# 3V3-CAN.net
KiCad netlist of a schematic drawn in Altium Designer
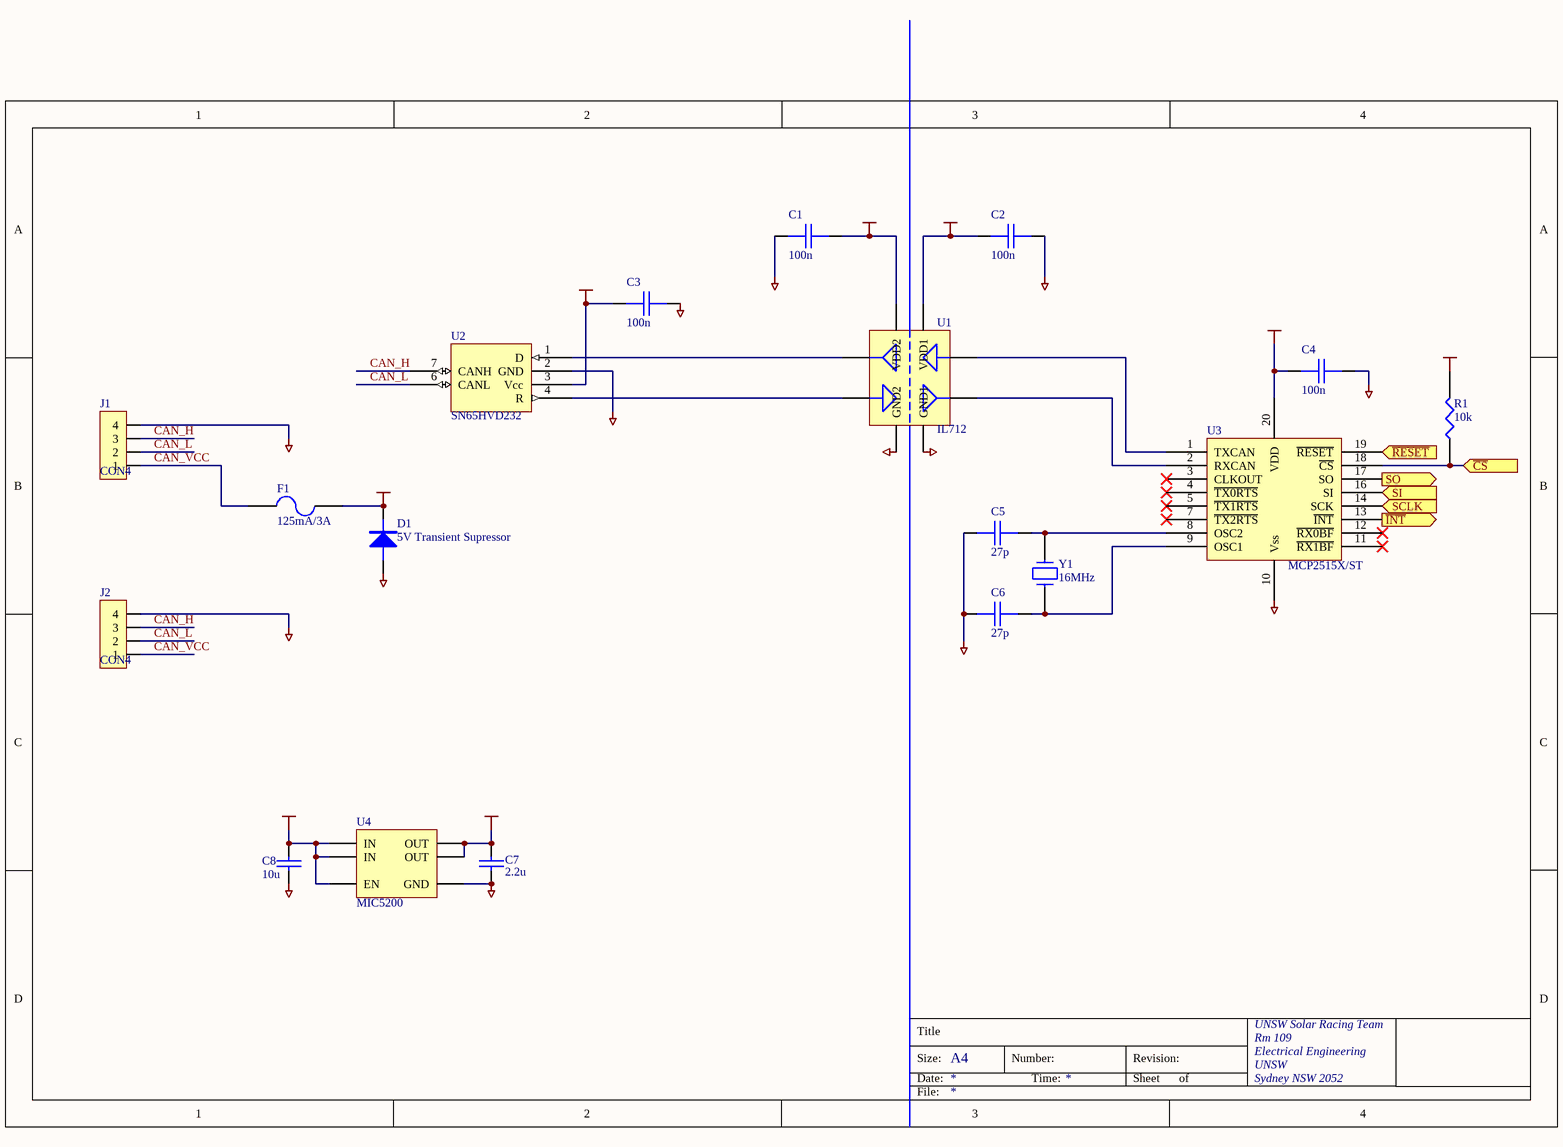
[diagram p0: 3V3-CAN.SchDoc]

(export (version "E")
  (design (tool "Eeschema 10.0.6"))
  (components
    (comp (ref "C1")
      (value "100n")
      (footprint "0603")
      (description "Capacitor")
      (libsource (lib "*") (part "CAP"))
    )
    (comp (ref "C2")
      (value "100n")
      (footprint "0603")
      (description "Capacitor")
      (libsource (lib "*") (part "CAP"))
    )
    (comp (ref "C3")
      (value "100n")
      (footprint "0603")
      (description "Capacitor")
      (libsource (lib "*") (part "CAP"))
    )
    (comp (ref "C4")
      (value "100n")
      (footprint "0603")
      (description "Capacitor")
      (libsource (lib "*") (part "CAP"))
    )
    (comp (ref "C5")
      (value "27p")
      (footprint "0603")
      (description "Capacitor")
      (libsource (lib "*") (part "CAP"))
    )
    (comp (ref "C6")
      (value "27p")
      (footprint "0603")
      (description "Capacitor")
      (libsource (lib "*") (part "CAP"))
    )
    (comp (ref "C7")
      (value "2.2u")
      (footprint "MCCT-CASEA")
      (description "Capacitor")
      (libsource (lib "") (part "CAP_1"))
    )
    (comp (ref "C8")
      (value "10u")
      (footprint "MCCT-CASEB")
      (description "Capacitor")
      (libsource (lib "") (part "CAP_1"))
    )
    (comp (ref "D1")
      (value "5V Transient Supressor")
      (footprint "SMA")
      (description "Diode")
      (libsource (lib "RCLDQ") (part "DIODE"))
    )
    (comp (ref "F1")
      (value "125mA/3A")
      (footprint "LITTELFUSE-154")
      (description "Fuse")
      (libsource (lib "*") (part "FUSE2"))
    )
    (comp (ref "J1")
      (value "CON4")
      (footprint "WEIDMULLER-SL3.5/4/90G")
      (description "Connector")
      (libsource (lib "Connectors") (part "CON4"))
    )
    (comp (ref "J2")
      (value "CON4")
      (footprint "WEIDMULLER-SL3.5/4/90G")
      (description "Connector")
      (libsource (lib "Connectors") (part "CON4"))
    )
    (comp (ref "R1") (value "10k") (footprint "0603") (libsource (lib "*") (part "RES1")))
    (comp (ref "U1")
      (value "IL712")
      (footprint "SO8")
      (description "IL712 Optoisolator - www.nve.com")
      (fields (field (name "PART FIELD 4") "simon.cope@tradetech.co.nz"))
      (libsource (lib "*") (part "IL712"))
    )
    (comp (ref "U2")
      (value "SN65HVD232")
      (footprint "SO8")
      (description "3.3V CAN Transciever")
      (libsource (lib "*") (part "SN65HVD232"))
    )
    (comp (ref "U3")
      (value "MCP2515X/ST")
      (footprint "TSSOP20")
      (description "MCP2510 CAN Controller")
      (libsource (lib "CAN") (part "MCP2515X/ST"))
    )
    (comp (ref "U4")
      (value "MIC5200")
      (footprint "SO8")
      (description "MIC5200 - SO8")
      (libsource (lib "*") (part "MIC5200"))
    )
    (comp (ref "Y1")
      (value "16MHz")
      (footprint "HC49/4H")
      (description "Crystal")
      (libsource (lib "*") (part "CRYSTAL"))
    )
  )
  (nets
    (net (code "1") (name "/CAN_H") (class "Default")
      (node (ref "J1") (pin "3") (pinfunction "3_3") (pintype "passive"))
      (node (ref "J2") (pin "3") (pinfunction "3_3") (pintype "passive"))
      (node (ref "U2") (pin "7") (pinfunction "CANH_7") (pintype "bidirectional"))
    )
    (net (code "2") (name "/CAN_L") (class "Default")
      (node (ref "J1") (pin "2") (pinfunction "2_2") (pintype "passive"))
      (node (ref "J2") (pin "2") (pinfunction "2_2") (pintype "passive"))
      (node (ref "U2") (pin "6") (pinfunction "CANL_6") (pintype "bidirectional"))
    )
    (net (code "3") (name "/CAN_VCC") (class "Default")
      (node (ref "F1") (pin "1") (pinfunction "1_1") (pintype "passive"))
      (node (ref "J1") (pin "1") (pinfunction "1_1") (pintype "passive"))
      (node (ref "J2") (pin "1") (pinfunction "1_1") (pintype "passive"))
    )
    (net (code "4") (name "/SCLK") (class "Default")
      (node (ref "U3") (pin "14") (pinfunction "SCK_14") (pintype "passive"))
    )
    (net (code "5") (name "/SI") (class "Default")
      (node (ref "U3") (pin "16") (pinfunction "SI_16") (pintype "passive"))
    )
    (net (code "6") (name "/SO") (class "Default")
      (node (ref "U3") (pin "17") (pinfunction "SO_17") (pintype "passive"))
    )
    (net (code "7") (name "/~{CS}") (class "Default")
      (node (ref "R1") (pin "1") (pinfunction "1_1") (pintype "passive"))
      (node (ref "U3") (pin "18") (pinfunction "~{CS}_18") (pintype "passive"))
    )
    (net (code "8") (name "/~{INT}") (class "Default")
      (node (ref "U3") (pin "13") (pinfunction "~{INT}_13") (pintype "passive"))
    )
    (net (code "9") (name "/~{RESET}") (class "Default")
      (node (ref "U3") (pin "19") (pinfunction "~{RESET}_19") (pintype "passive"))
    )
    (net (code "10") (name "3V3") (class "Default")
      (node (ref "C2") (pin "2") (pinfunction "2_2") (pintype "passive"))
      (node (ref "C4") (pin "1") (pinfunction "1_1") (pintype "passive"))
      (node (ref "R1") (pin "2") (pinfunction "2_2") (pintype "passive"))
      (node (ref "U1") (pin "1") (pinfunction "VDD1_1") (pintype "passive"))
      (node (ref "U3") (pin "20") (pinfunction "VDD_20") (pintype "passive"))
    )
    (net (code "11") (name "CAN_3V3") (class "Default")
      (node (ref "C1") (pin "2") (pinfunction "2_2") (pintype "passive"))
      (node (ref "C3") (pin "2") (pinfunction "2_2") (pintype "passive"))
      (node (ref "C7") (pin "2") (pinfunction "2_2") (pintype "passive"))
      (node (ref "U1") (pin "8") (pinfunction "VDD2_8") (pintype "passive"))
      (node (ref "U2") (pin "3") (pinfunction "Vcc_3") (pintype "power_in"))
      (node (ref "U4") (pin "1") (pinfunction "OUT_1") (pintype "passive"))
      (node (ref "U4") (pin "2") (pinfunction "OUT_2") (pintype "passive"))
    )
    (net (code "12") (name "CAN_5V") (class "Default")
      (node (ref "C8") (pin "1") (pinfunction "1_1") (pintype "passive"))
      (node (ref "D1") (pin "K") (pinfunction "K_K") (pintype "passive"))
      (node (ref "F1") (pin "2") (pinfunction "2_2") (pintype "passive"))
      (node (ref "U4") (pin "5") (pinfunction "EN_5") (pintype "passive"))
      (node (ref "U4") (pin "7") (pinfunction "IN_7") (pintype "passive"))
      (node (ref "U4") (pin "8") (pinfunction "IN_8") (pintype "passive"))
    )
    (net (code "13") (name "CAN_GND") (class "Default")
      (node (ref "C1") (pin "1") (pinfunction "1_1") (pintype "passive"))
      (node (ref "C3") (pin "1") (pinfunction "1_1") (pintype "passive"))
      (node (ref "C7") (pin "1") (pinfunction "1_1") (pintype "passive"))
      (node (ref "C8") (pin "2") (pinfunction "2_2") (pintype "passive"))
      (node (ref "D1") (pin "A") (pinfunction "A_A") (pintype "passive"))
      (node (ref "J1") (pin "4") (pinfunction "4_4") (pintype "passive"))
      (node (ref "J2") (pin "4") (pinfunction "4_4") (pintype "passive"))
      (node (ref "U1") (pin "5") (pinfunction "GND2_5") (pintype "passive"))
      (node (ref "U2") (pin "2") (pinfunction "GND_2") (pintype "power_in"))
      (node (ref "U4") (pin "4") (pinfunction "GND_4") (pintype "passive"))
    )
    (net (code "14") (name "GND") (class "Default")
      (node (ref "C2") (pin "1") (pinfunction "1_1") (pintype "passive"))
      (node (ref "C4") (pin "2") (pinfunction "2_2") (pintype "passive"))
      (node (ref "C5") (pin "1") (pinfunction "1_1") (pintype "passive"))
      (node (ref "C6") (pin "1") (pinfunction "1_1") (pintype "passive"))
      (node (ref "U1") (pin "4") (pinfunction "GND1_4") (pintype "passive"))
      (node (ref "U3") (pin "10") (pinfunction "Vss_10") (pintype "passive"))
    )
    (net (code "15") (name "Net-(U1-IN1)") (class "Default")
      (node (ref "U1") (pin "2") (pinfunction "IN1_2") (pintype "passive"))
      (node (ref "U3") (pin "1") (pinfunction "TXCAN_1") (pintype "passive"))
    )
    (net (code "16") (name "Net-(U1-IN2)") (class "Default")
      (node (ref "U1") (pin "6") (pinfunction "IN2_6") (pintype "passive"))
      (node (ref "U2") (pin "4") (pinfunction "R_4") (pintype "output"))
    )
    (net (code "17") (name "Net-(U1-OUT1)") (class "Default")
      (node (ref "U1") (pin "7") (pinfunction "OUT1_7") (pintype "passive"))
      (node (ref "U2") (pin "1") (pinfunction "D_1") (pintype "input"))
    )
    (net (code "18") (name "Net-(U1-OUT2)") (class "Default")
      (node (ref "U1") (pin "3") (pinfunction "OUT2_3") (pintype "passive"))
      (node (ref "U3") (pin "2") (pinfunction "RXCAN_2") (pintype "passive"))
    )
    (net (code "19") (name "Net-(U3-OSC1)") (class "Default")
      (node (ref "C6") (pin "2") (pinfunction "2_2") (pintype "passive"))
      (node (ref "U3") (pin "9") (pinfunction "OSC1_9") (pintype "passive"))
      (node (ref "Y1") (pin "2") (pinfunction "2_2") (pintype "passive"))
    )
    (net (code "20") (name "Net-(U3-OSC2)") (class "Default")
      (node (ref "C5") (pin "2") (pinfunction "2_2") (pintype "passive"))
      (node (ref "U3") (pin "8") (pinfunction "OSC2_8") (pintype "passive"))
      (node (ref "Y1") (pin "1") (pinfunction "1_1") (pintype "passive"))
    )
    (net (code "21") (name "unconnected-(U3-CLKOUT-Pad3)") (class "Default")
      (node (ref "U3") (pin "3") (pinfunction "CLKOUT_3") (pintype "passive+no_connect"))
    )
    (net (code "22") (name "unconnected-(U3-~{RX0BF}-Pad12)") (class "Default")
      (node (ref "U3") (pin "12") (pinfunction "~{RX0BF}_12") (pintype "passive+no_connect"))
    )
    (net (code "23") (name "unconnected-(U3-~{RX1BF}-Pad11)") (class "Default")
      (node (ref "U3") (pin "11") (pinfunction "~{RX1BF}_11") (pintype "passive+no_connect"))
    )
    (net (code "24") (name "unconnected-(U3-~{TX0RTS}-Pad4)") (class "Default")
      (node (ref "U3") (pin "4") (pinfunction "~{TX0RTS}_4") (pintype "passive+no_connect"))
    )
    (net (code "25") (name "unconnected-(U3-~{TX1RTS}-Pad5)") (class "Default")
      (node (ref "U3") (pin "5") (pinfunction "~{TX1RTS}_5") (pintype "passive+no_connect"))
    )
    (net (code "26") (name "unconnected-(U3-~{TX2RTS}-Pad7)") (class "Default")
      (node (ref "U3") (pin "7") (pinfunction "~{TX2RTS}_7") (pintype "passive+no_connect"))
    )
  )
)
